# MIDI_CV_Converter.net
KiCad netlist of a schematic drawn in Altium Designer
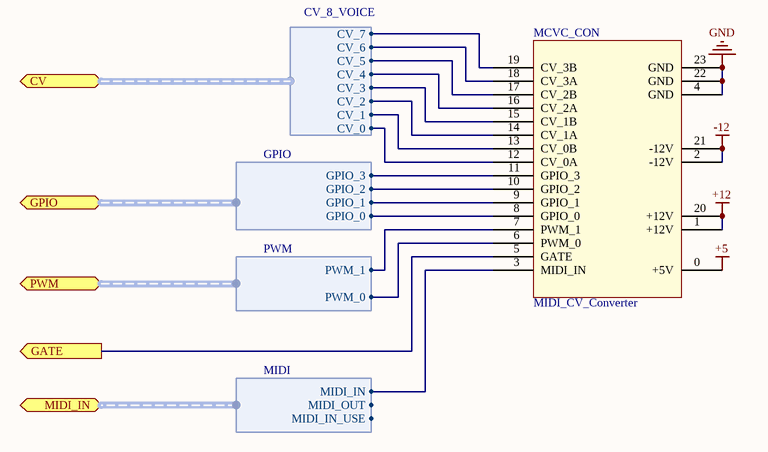
[diagram p0: MIDI_CV_Converter.SchDoc]

(export (version "E")
  (design (tool "Eeschema 10.0.6"))
  (components
    (comp (ref "MCVC_CON")
      (value "MIDI_CV_Converter")
      (footprint "MIDI-CV CONVERTER SOCKET")
      (libsource (lib "Gary_Module") (part "MIDI_CV_Converter"))
    )
  )
  (nets
    (net (code "5") (name "+5") (class "Default")
      (node (ref "MCVC_CON") (pin "0") (pinfunction "+5V_0") (pintype "passive"))
    )
    (net (code "6") (name "+12") (class "Default")
      (node (ref "MCVC_CON") (pin "1") (pinfunction "+12V_1") (pintype "passive"))
      (node (ref "MCVC_CON") (pin "20") (pinfunction "+12V_20") (pintype "passive"))
    )
    (net (code "7") (name "-12") (class "Default")
      (node (ref "MCVC_CON") (pin "2") (pinfunction "-12V_2") (pintype "passive"))
      (node (ref "MCVC_CON") (pin "21") (pinfunction "-12V_21") (pintype "passive"))
    )
    (net (code "8") (name "/CV_0") (class "Default")
      (node (ref "MCVC_CON") (pin "12") (pinfunction "CV_0A_12") (pintype "passive"))
    )
    (net (code "9") (name "/CV_1") (class "Default")
      (node (ref "MCVC_CON") (pin "13") (pinfunction "CV_0B_13") (pintype "passive"))
    )
    (net (code "10") (name "/CV_2") (class "Default")
      (node (ref "MCVC_CON") (pin "14") (pinfunction "CV_1A_14") (pintype "passive"))
    )
    (net (code "11") (name "/CV_3") (class "Default")
      (node (ref "MCVC_CON") (pin "15") (pinfunction "CV_1B_15") (pintype "passive"))
    )
    (net (code "12") (name "/CV_4") (class "Default")
      (node (ref "MCVC_CON") (pin "16") (pinfunction "CV_2A_16") (pintype "passive"))
    )
    (net (code "13") (name "/CV_5") (class "Default")
      (node (ref "MCVC_CON") (pin "17") (pinfunction "CV_2B_17") (pintype "passive"))
    )
    (net (code "14") (name "/CV_6") (class "Default")
      (node (ref "MCVC_CON") (pin "18") (pinfunction "CV_3A_18") (pintype "passive"))
    )
    (net (code "15") (name "/CV_7") (class "Default")
      (node (ref "MCVC_CON") (pin "19") (pinfunction "CV_3B_19") (pintype "passive"))
    )
    (net (code "16") (name "/GATE") (class "Default")
      (node (ref "MCVC_CON") (pin "5") (pinfunction "GATE_5") (pintype "passive"))
    )
    (net (code "17") (name "/GPIO_0") (class "Default")
      (node (ref "MCVC_CON") (pin "8") (pinfunction "GPIO_0_8") (pintype "passive"))
    )
    (net (code "18") (name "/GPIO_1") (class "Default")
      (node (ref "MCVC_CON") (pin "9") (pinfunction "GPIO_1_9") (pintype "passive"))
    )
    (net (code "19") (name "/GPIO_2") (class "Default")
      (node (ref "MCVC_CON") (pin "10") (pinfunction "GPIO_2_10") (pintype "passive"))
    )
    (net (code "20") (name "/GPIO_3") (class "Default")
      (node (ref "MCVC_CON") (pin "11") (pinfunction "GPIO_3_11") (pintype "passive"))
    )
    (net (code "21") (name "/PWM_0") (class "Default")
      (node (ref "MCVC_CON") (pin "6") (pinfunction "PWM_0_6") (pintype "passive"))
    )
    (net (code "22") (name "/PWM_1") (class "Default")
      (node (ref "MCVC_CON") (pin "7") (pinfunction "PWM_1_7") (pintype "passive"))
    )
    (net (code "27") (name "GND") (class "Default")
      (node (ref "MCVC_CON") (pin "22") (pinfunction "GND_22") (pintype "passive"))
      (node (ref "MCVC_CON") (pin "23") (pinfunction "GND_23") (pintype "passive"))
      (node (ref "MCVC_CON") (pin "4") (pinfunction "GND_4") (pintype "passive"))
    )
    (net (code "28") (name "unconnected-(MCVC_CON-MIDI_IN-Pad3)") (class "Default")
      (node (ref "MCVC_CON") (pin "3") (pinfunction "MIDI_IN_3") (pintype "passive"))
    )
  )
)
